# 04-ETHERNET.net
KiCad netlist of a schematic drawn in Altium Designer
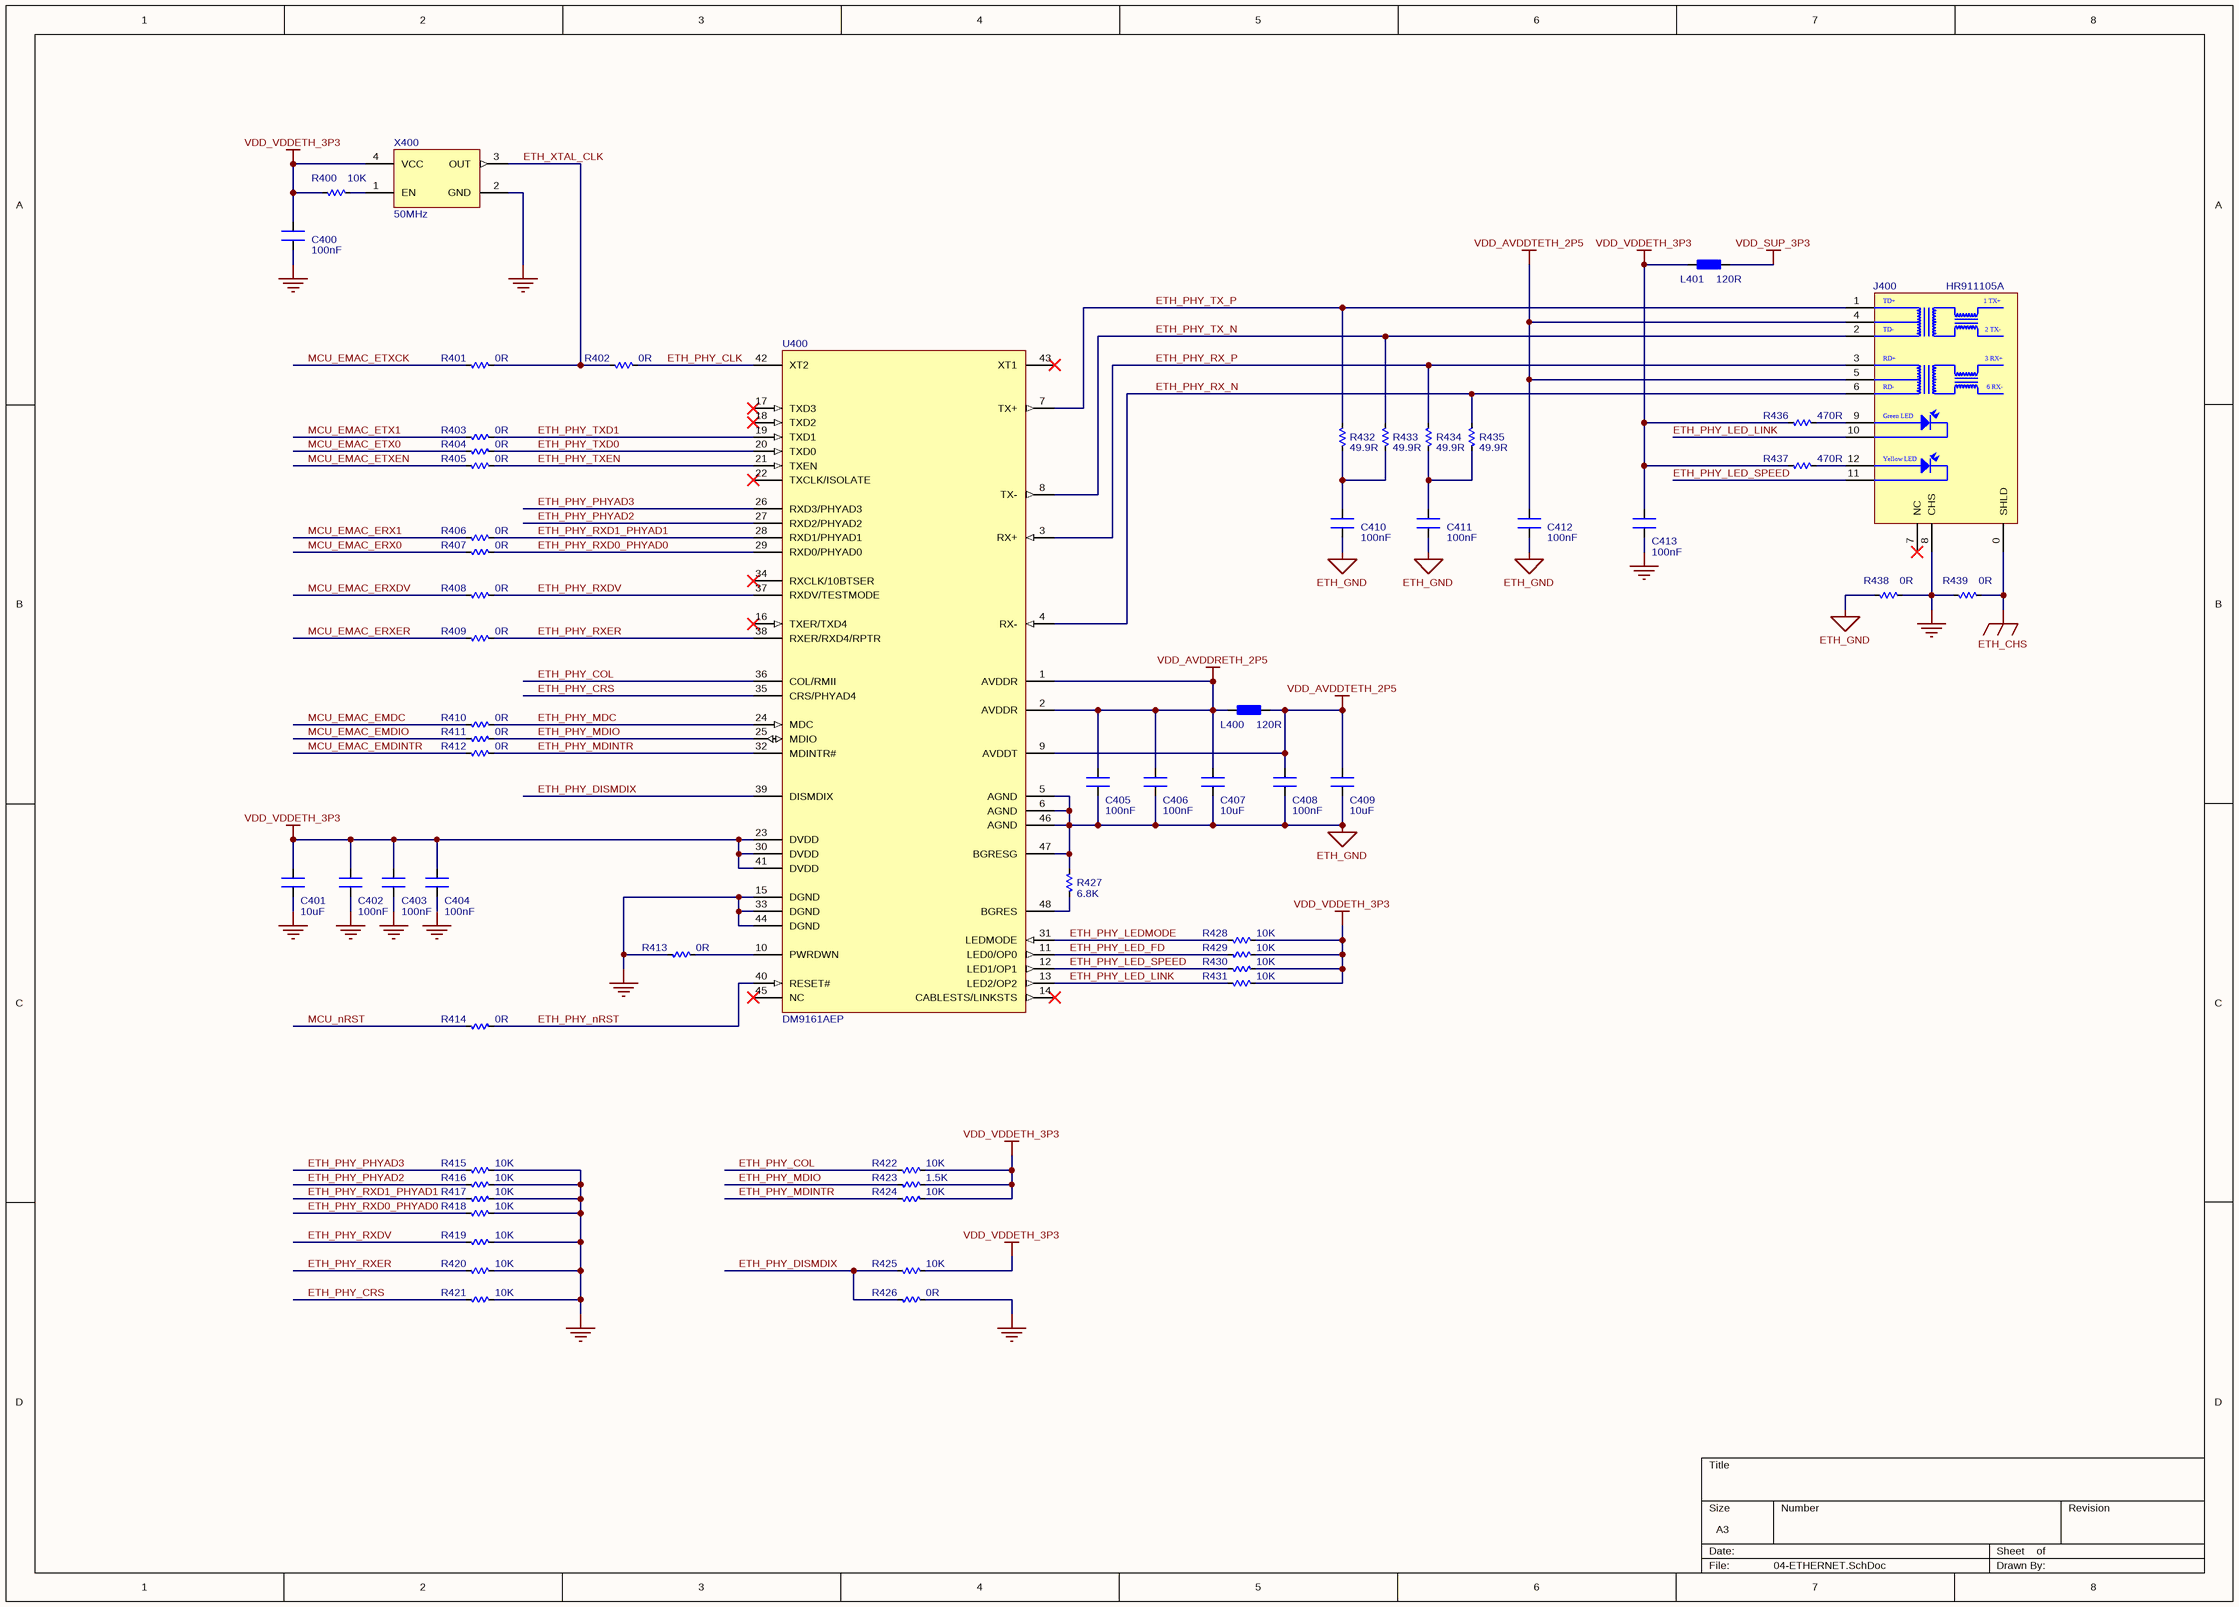
[diagram p0: 04-ETHERNET.SchDoc]

(export (version "E")
  (design (tool "Eeschema 10.0.6"))
  (components
    (comp (ref "C400")
      (value "100nF")
      (footprint "CN-SMD-0603")
      (description "Ceramic Capacitor SMD 0603 100nF ±20% 10V")
      (fields (field (name "Comment") "Capacitor"))
      (libsource (lib "AS50") (part "Cap"))
    )
    (comp (ref "C401")
      (value "10uF")
      (footprint "CN-SMD-0603")
      (description "Ceramic Capacitor SMD 0603 10uF ±20% 10V")
      (fields (field (name "Comment") "Capacitor"))
      (libsource (lib "AS50") (part "Cap"))
    )
    (comp (ref "C402")
      (value "100nF")
      (footprint "CN-SMD-0603")
      (description "Ceramic Capacitor SMD 0603 100nF ±20% 10V")
      (fields (field (name "Comment") "Capacitor"))
      (libsource (lib "AS50") (part "Cap"))
    )
    (comp (ref "C403")
      (value "100nF")
      (footprint "CN-SMD-0603")
      (description "Ceramic Capacitor SMD 0603 100nF ±20% 10V")
      (fields (field (name "Comment") "Capacitor"))
      (libsource (lib "AS50") (part "Cap"))
    )
    (comp (ref "C404")
      (value "100nF")
      (footprint "CN-SMD-0603")
      (description "Ceramic Capacitor SMD 0603 100nF ±20% 10V")
      (fields (field (name "Comment") "Capacitor"))
      (libsource (lib "AS50") (part "Cap"))
    )
    (comp (ref "C405")
      (value "100nF")
      (footprint "CN-SMD-0603")
      (description "Ceramic Capacitor SMD 0603 100nF ±20% 10V")
      (fields (field (name "Comment") "Capacitor"))
      (libsource (lib "AS50") (part "Cap"))
    )
    (comp (ref "C406")
      (value "100nF")
      (footprint "CN-SMD-0603")
      (description "Ceramic Capacitor SMD 0603 100nF ±20% 10V")
      (fields (field (name "Comment") "Capacitor"))
      (libsource (lib "AS50") (part "Cap"))
    )
    (comp (ref "C407")
      (value "10uF")
      (footprint "CN-SMD-0603")
      (description "Ceramic Capacitor SMD 0603 10uF ±20% 10V")
      (fields (field (name "Comment") "Capacitor"))
      (libsource (lib "AS50") (part "Cap"))
    )
    (comp (ref "C408")
      (value "100nF")
      (footprint "CN-SMD-0603")
      (description "Ceramic Capacitor SMD 0603 100nF ±20% 10V")
      (fields (field (name "Comment") "Capacitor"))
      (libsource (lib "AS50") (part "Cap"))
    )
    (comp (ref "C409")
      (value "10uF")
      (footprint "CN-SMD-0603")
      (description "Ceramic Capacitor SMD 0603 10uF ±20% 10V")
      (fields (field (name "Comment") "Capacitor"))
      (libsource (lib "AS50") (part "Cap"))
    )
    (comp (ref "C410")
      (value "100nF")
      (footprint "CN-SMD-0603")
      (description "Ceramic Capacitor SMD 0603 100nF ±20% 10V")
      (fields (field (name "Comment") "Capacitor"))
      (libsource (lib "AS50") (part "Cap"))
    )
    (comp (ref "C411")
      (value "100nF")
      (footprint "CN-SMD-0603")
      (description "Ceramic Capacitor SMD 0603 100nF ±20% 10V")
      (fields (field (name "Comment") "Capacitor"))
      (libsource (lib "AS50") (part "Cap"))
    )
    (comp (ref "C412")
      (value "100nF")
      (footprint "CN-SMD-0603")
      (description "Ceramic Capacitor SMD 0603 100nF ±20% 10V")
      (fields (field (name "Comment") "Capacitor"))
      (libsource (lib "AS50") (part "Cap"))
    )
    (comp (ref "C413")
      (value "100nF")
      (footprint "CN-SMD-0603")
      (description "Ceramic Capacitor SMD 0603 100nF ±20% 10V")
      (fields (field (name "Comment") "Capacitor"))
      (libsource (lib "AS50") (part "Cap"))
    )
    (comp (ref "J400")
      (value "HR911105A")
      (footprint "RJ-45_HR911105A")
      (description "Single port RJ45 Connector with Integrated Magnetics and LED for 10/100-BaseTX NIC Applications")
      (libsource (lib "AS50") (part "HR911105A"))
    )
    (comp (ref "L400")
      (value "120R")
      (footprint "L-SMD-0603")
      (description "Ferrite bead SMD 0603 120 Ohm @100MHz")
      (fields (field (name "Comment") "Ferrite bead"))
      (libsource (lib "AS50") (part "Ferrite bead"))
    )
    (comp (ref "L401")
      (value "120R")
      (footprint "L-SMD-0603")
      (description "Ferrite bead SMD 0603 120 Ohm @100MHz")
      (fields (field (name "Comment") "Ferrite bead"))
      (libsource (lib "AS50") (part "Ferrite bead"))
    )
    (comp (ref "R400")
      (value "10K")
      (footprint "RES-SMD-0603")
      (description "Resistor SMD 0603 10K 1% 0.1W")
      (fields (field (name "Comment") "Resistor"))
      (libsource (lib "AS50") (part "Res"))
    )
    (comp (ref "R401")
      (value "0R")
      (footprint "RES-SMD-0603")
      (description "Resistor SMD 0603 0R 1% 0.1W")
      (fields (field (name "Comment") "Resistor"))
      (libsource (lib "AS50") (part "Res"))
    )
    (comp (ref "R402")
      (value "0R")
      (footprint "RES-SMD-0603")
      (description "Resistor SMD 0603 0R 1% 0.1W")
      (fields (field (name "Comment") "Resistor"))
      (libsource (lib "AS50") (part "Res"))
    )
    (comp (ref "R403")
      (value "0R")
      (footprint "RES-SMD-0603")
      (description "Resistor SMD 0603 0R 1% 0.1W")
      (fields (field (name "Comment") "Resistor"))
      (libsource (lib "AS50") (part "Res"))
    )
    (comp (ref "R404")
      (value "0R")
      (footprint "RES-SMD-0603")
      (description "Resistor SMD 0603 0R 1% 0.1W")
      (fields (field (name "Comment") "Resistor"))
      (libsource (lib "AS50") (part "Res"))
    )
    (comp (ref "R405")
      (value "0R")
      (footprint "RES-SMD-0603")
      (description "Resistor SMD 0603 0R 1% 0.1W")
      (fields (field (name "Comment") "Resistor"))
      (libsource (lib "AS50") (part "Res"))
    )
    (comp (ref "R406")
      (value "0R")
      (footprint "RES-SMD-0603")
      (description "Resistor SMD 0603 0R 1% 0.1W")
      (fields (field (name "Comment") "Resistor"))
      (libsource (lib "AS50") (part "Res"))
    )
    (comp (ref "R407")
      (value "0R")
      (footprint "RES-SMD-0603")
      (description "Resistor SMD 0603 0R 1% 0.1W")
      (fields (field (name "Comment") "Resistor"))
      (libsource (lib "AS50") (part "Res"))
    )
    (comp (ref "R408")
      (value "0R")
      (footprint "RES-SMD-0603")
      (description "Resistor SMD 0603 0R 1% 0.1W")
      (fields (field (name "Comment") "Resistor"))
      (libsource (lib "AS50") (part "Res"))
    )
    (comp (ref "R409")
      (value "0R")
      (footprint "RES-SMD-0603")
      (description "Resistor SMD 0603 0R 1% 0.1W")
      (fields (field (name "Comment") "Resistor"))
      (libsource (lib "AS50") (part "Res"))
    )
    (comp (ref "R410")
      (value "0R")
      (footprint "RES-SMD-0603")
      (description "Resistor SMD 0603 0R 1% 0.1W")
      (fields (field (name "Comment") "Resistor"))
      (libsource (lib "AS50") (part "Res"))
    )
    (comp (ref "R411")
      (value "0R")
      (footprint "RES-SMD-0603")
      (description "Resistor SMD 0603 0R 1% 0.1W")
      (fields (field (name "Comment") "Resistor"))
      (libsource (lib "AS50") (part "Res"))
    )
    (comp (ref "R412")
      (value "0R")
      (footprint "RES-SMD-0603")
      (description "Resistor SMD 0603 0R 1% 0.1W")
      (fields (field (name "Comment") "Resistor"))
      (libsource (lib "AS50") (part "Res"))
    )
    (comp (ref "R413")
      (value "0R")
      (footprint "RES-SMD-0603")
      (description "Resistor SMD 0603 0R 1% 0.1W")
      (fields (field (name "Comment") "Resistor"))
      (libsource (lib "AS50") (part "Res"))
    )
    (comp (ref "R414")
      (value "0R")
      (footprint "RES-SMD-0603")
      (description "Resistor SMD 0603 0R 1% 0.1W")
      (fields (field (name "Comment") "Resistor"))
      (libsource (lib "AS50") (part "Res"))
    )
    (comp (ref "R415")
      (value "10K")
      (footprint "RES-SMD-0603")
      (description "Resistor SMD 0603 10K 1% 0.1W")
      (fields (field (name "Comment") "Resistor"))
      (libsource (lib "AS50") (part "Res"))
    )
    (comp (ref "R416")
      (value "10K")
      (footprint "RES-SMD-0603")
      (description "Resistor SMD 0603 10K 1% 0.1W")
      (fields (field (name "Comment") "Resistor"))
      (libsource (lib "AS50") (part "Res"))
    )
    (comp (ref "R417")
      (value "10K")
      (footprint "RES-SMD-0603")
      (description "Resistor SMD 0603 10K 1% 0.1W")
      (fields (field (name "Comment") "Resistor"))
      (libsource (lib "AS50") (part "Res"))
    )
    (comp (ref "R418")
      (value "10K")
      (footprint "RES-SMD-0603")
      (description "Resistor SMD 0603 10K 1% 0.1W")
      (fields (field (name "Comment") "Resistor"))
      (libsource (lib "AS50") (part "Res"))
    )
    (comp (ref "R419")
      (value "10K")
      (footprint "RES-SMD-0603")
      (description "Resistor SMD 0603 10K 1% 0.1W")
      (fields (field (name "Comment") "Resistor"))
      (libsource (lib "AS50") (part "Res"))
    )
    (comp (ref "R420")
      (value "10K")
      (footprint "RES-SMD-0603")
      (description "Resistor SMD 0603 10K 1% 0.1W")
      (fields (field (name "Comment") "Resistor"))
      (libsource (lib "AS50") (part "Res"))
    )
    (comp (ref "R421")
      (value "10K")
      (footprint "RES-SMD-0603")
      (description "Resistor SMD 0603 10K 1% 0.1W")
      (fields (field (name "Comment") "Resistor"))
      (libsource (lib "AS50") (part "Res"))
    )
    (comp (ref "R422")
      (value "10K")
      (footprint "RES-SMD-0603")
      (description "Resistor SMD 0603 10K 1% 0.1W")
      (fields (field (name "Comment") "Resistor"))
      (libsource (lib "AS50") (part "Res"))
    )
    (comp (ref "R423")
      (value "1.5K")
      (footprint "RES-SMD-0603")
      (description "Resistor SMD 0603 1.5K 1% 0.1W")
      (fields (field (name "Comment") "Resistor"))
      (libsource (lib "AS50") (part "Res"))
    )
    (comp (ref "R424")
      (value "10K")
      (footprint "RES-SMD-0603")
      (description "Resistor SMD 0603 10K 1% 0.1W")
      (fields (field (name "Comment") "Resistor"))
      (libsource (lib "AS50") (part "Res"))
    )
    (comp (ref "R425")
      (value "10K")
      (footprint "RES-SMD-0603")
      (description "Resistor SMD 0603 10K 1% 0.1W")
      (fields (field (name "Comment") "Resistor"))
      (libsource (lib "AS50") (part "Res"))
    )
    (comp (ref "R426")
      (value "0R")
      (footprint "RES-SMD-0603")
      (description "Resistor SMD 0603 0R 1% 0.1W")
      (fields (field (name "Comment") "Resistor"))
      (libsource (lib "AS50") (part "Res"))
    )
    (comp (ref "R427")
      (value "6.8K")
      (footprint "RES-SMD-0603")
      (description "Resistor SMD 0603 6.8K 1% 0.1W")
      (fields (field (name "Comment") "Resistor"))
      (libsource (lib "AS50") (part "Res"))
    )
    (comp (ref "R428")
      (value "10K")
      (footprint "RES-SMD-0603")
      (description "Resistor SMD 0603 10K 1% 0.1W")
      (fields (field (name "Comment") "Resistor"))
      (libsource (lib "AS50") (part "Res"))
    )
    (comp (ref "R429")
      (value "10K")
      (footprint "RES-SMD-0603")
      (description "Resistor SMD 0603 10K 1% 0.1W")
      (fields (field (name "Comment") "Resistor"))
      (libsource (lib "AS50") (part "Res"))
    )
    (comp (ref "R430")
      (value "10K")
      (footprint "RES-SMD-0603")
      (description "Resistor SMD 0603 10K 1% 0.1W")
      (fields (field (name "Comment") "Resistor"))
      (libsource (lib "AS50") (part "Res"))
    )
    (comp (ref "R431")
      (value "10K")
      (footprint "RES-SMD-0603")
      (description "Resistor SMD 0603 10K 1% 0.1W")
      (fields (field (name "Comment") "Resistor"))
      (libsource (lib "AS50") (part "Res"))
    )
    (comp (ref "R432")
      (value "49.9R")
      (footprint "RES-SMD-0603")
      (description "Resistor SMD 0603 49.9R 1% 0.1W")
      (fields (field (name "Comment") "Resistor"))
      (libsource (lib "AS50") (part "Res"))
    )
    (comp (ref "R433")
      (value "49.9R")
      (footprint "RES-SMD-0603")
      (description "Resistor SMD 0603 49.9R 1% 0.1W")
      (fields (field (name "Comment") "Resistor"))
      (libsource (lib "AS50") (part "Res"))
    )
    (comp (ref "R434")
      (value "49.9R")
      (footprint "RES-SMD-0603")
      (description "Resistor SMD 0603 49.9R 1% 0.1W")
      (fields (field (name "Comment") "Resistor"))
      (libsource (lib "AS50") (part "Res"))
    )
    (comp (ref "R435")
      (value "49.9R")
      (footprint "RES-SMD-0603")
      (description "Resistor SMD 0603 49.9R 1% 0.1W")
      (fields (field (name "Comment") "Resistor"))
      (libsource (lib "AS50") (part "Res"))
    )
    (comp (ref "R436")
      (value "470R")
      (footprint "RES-SMD-0603")
      (description "Resistor SMD 0603 470R 1% 0.1W")
      (fields (field (name "Comment") "Resistor"))
      (libsource (lib "AS50") (part "Res"))
    )
    (comp (ref "R437")
      (value "470R")
      (footprint "RES-SMD-0603")
      (description "Resistor SMD 0603 470R 1% 0.1W")
      (fields (field (name "Comment") "Resistor"))
      (libsource (lib "AS50") (part "Res"))
    )
    (comp (ref "R438")
      (value "0R")
      (footprint "RES-SMD-0603")
      (description "Resistor SMD 0603 0R 1% 0.1W")
      (fields (field (name "Comment") "Resistor"))
      (libsource (lib "AS50") (part "Res"))
    )
    (comp (ref "R439")
      (value "0R")
      (footprint "RES-SMD-1206")
      (description "Resistor SMD 1206 0R 1% 0.5W")
      (fields (field (name "Comment") "Resistor"))
      (libsource (lib "AS50") (part "Res"))
    )
    (comp (ref "U400")
      (value "DM9161AEP")
      (footprint "LQFP50P900X900X160-48N")
      (description "DAVICOM 10/100Mbps Fast Ethernet Physical Layer Single Chip Transceiver")
      (libsource (lib "AS50") (part "DM9161AEP"))
    )
    (comp (ref "X400")
      (value "50MHz")
      (footprint "XT-SMD-3225-4P")
      (description "Crystal Oscillator SMD3225 4-pin")
      (libsource (lib "AS50") (part "XT4_2"))
    )
  )
  (nets
    (net (code "1") (name "/ETH_PHY_CLK") (class "Default")
      (node (ref "R402") (pin "1") (pinfunction "1_1") (pintype "passive"))
      (node (ref "U400") (pin "42") (pinfunction "XT2_42") (pintype "passive"))
    )
    (net (code "2") (name "/ETH_PHY_COL") (class "Default")
      (node (ref "R422") (pin "2") (pinfunction "2_2") (pintype "passive"))
      (node (ref "U400") (pin "36") (pinfunction "COL/RMII_36") (pintype "passive"))
    )
    (net (code "3") (name "/ETH_PHY_CRS") (class "Default")
      (node (ref "R421") (pin "2") (pinfunction "2_2") (pintype "passive"))
      (node (ref "U400") (pin "35") (pinfunction "CRS/PHYAD4_35") (pintype "passive"))
    )
    (net (code "4") (name "/ETH_PHY_DISMDIX") (class "Default")
      (node (ref "R425") (pin "2") (pinfunction "2_2") (pintype "passive"))
      (node (ref "R426") (pin "2") (pinfunction "2_2") (pintype "passive"))
      (node (ref "U400") (pin "39") (pinfunction "DISMDIX_39") (pintype "passive"))
    )
    (net (code "5") (name "/ETH_PHY_LEDMODE") (class "Default")
      (node (ref "R428") (pin "2") (pinfunction "2_2") (pintype "passive"))
      (node (ref "U400") (pin "31") (pinfunction "LEDMODE_31") (pintype "input"))
    )
    (net (code "6") (name "/ETH_PHY_LED_FD") (class "Default")
      (node (ref "R429") (pin "2") (pinfunction "2_2") (pintype "passive"))
      (node (ref "U400") (pin "11") (pinfunction "LED0/OP0_11") (pintype "output"))
    )
    (net (code "7") (name "/ETH_PHY_LED_LINK") (class "Default")
      (node (ref "J400") (pin "10") (pinfunction "Green-_10") (pintype "passive"))
      (node (ref "R431") (pin "2") (pinfunction "2_2") (pintype "passive"))
      (node (ref "U400") (pin "13") (pinfunction "LED2/OP2_13") (pintype "output"))
    )
    (net (code "8") (name "/ETH_PHY_LED_SPEED") (class "Default")
      (node (ref "J400") (pin "11") (pinfunction "Yellow-_11") (pintype "passive"))
      (node (ref "R430") (pin "2") (pinfunction "2_2") (pintype "passive"))
      (node (ref "U400") (pin "12") (pinfunction "LED1/OP1_12") (pintype "output"))
    )
    (net (code "9") (name "/ETH_PHY_MDC") (class "Default")
      (node (ref "R410") (pin "1") (pinfunction "1_1") (pintype "passive"))
      (node (ref "U400") (pin "24") (pinfunction "MDC_24") (pintype "input"))
    )
    (net (code "10") (name "/ETH_PHY_MDINTR") (class "Default")
      (node (ref "R412") (pin "1") (pinfunction "1_1") (pintype "passive"))
      (node (ref "R424") (pin "2") (pinfunction "2_2") (pintype "passive"))
      (node (ref "U400") (pin "32") (pinfunction "MDINTR#_32") (pintype "passive"))
    )
    (net (code "11") (name "/ETH_PHY_MDIO") (class "Default")
      (node (ref "R411") (pin "1") (pinfunction "1_1") (pintype "passive"))
      (node (ref "R423") (pin "2") (pinfunction "2_2") (pintype "passive"))
      (node (ref "U400") (pin "25") (pinfunction "MDIO_25") (pintype "bidirectional"))
    )
    (net (code "12") (name "/ETH_PHY_PHYAD2") (class "Default")
      (node (ref "R416") (pin "2") (pinfunction "2_2") (pintype "passive"))
      (node (ref "U400") (pin "27") (pinfunction "RXD2/PHYAD2_27") (pintype "passive"))
    )
    (net (code "13") (name "/ETH_PHY_PHYAD3") (class "Default")
      (node (ref "R415") (pin "2") (pinfunction "2_2") (pintype "passive"))
      (node (ref "U400") (pin "26") (pinfunction "RXD3/PHYAD3_26") (pintype "passive"))
    )
    (net (code "14") (name "/ETH_PHY_RXD0_PHYAD0") (class "Default")
      (node (ref "R407") (pin "1") (pinfunction "1_1") (pintype "passive"))
      (node (ref "R418") (pin "2") (pinfunction "2_2") (pintype "passive"))
      (node (ref "U400") (pin "29") (pinfunction "RXD0/PHYAD0_29") (pintype "passive"))
    )
    (net (code "15") (name "/ETH_PHY_RXD1_PHYAD1") (class "Default")
      (node (ref "R406") (pin "1") (pinfunction "1_1") (pintype "passive"))
      (node (ref "R417") (pin "2") (pinfunction "2_2") (pintype "passive"))
      (node (ref "U400") (pin "28") (pinfunction "RXD1/PHYAD1_28") (pintype "passive"))
    )
    (net (code "16") (name "/ETH_PHY_RXDV") (class "Default")
      (node (ref "R408") (pin "1") (pinfunction "1_1") (pintype "passive"))
      (node (ref "R419") (pin "2") (pinfunction "2_2") (pintype "passive"))
      (node (ref "U400") (pin "37") (pinfunction "RXDV/TESTMODE_37") (pintype "passive"))
    )
    (net (code "17") (name "/ETH_PHY_RXER") (class "Default")
      (node (ref "R409") (pin "1") (pinfunction "1_1") (pintype "passive"))
      (node (ref "R420") (pin "2") (pinfunction "2_2") (pintype "passive"))
      (node (ref "U400") (pin "38") (pinfunction "RXER/RXD4/RPTR_38") (pintype "passive"))
    )
    (net (code "18") (name "/ETH_PHY_RX_N") (class "Default")
      (node (ref "J400") (pin "6") (pinfunction "RD-_6") (pintype "passive"))
      (node (ref "R435") (pin "1") (pinfunction "1_1") (pintype "passive"))
      (node (ref "U400") (pin "4") (pinfunction "RX-_4") (pintype "input"))
    )
    (net (code "19") (name "/ETH_PHY_RX_P") (class "Default")
      (node (ref "J400") (pin "3") (pinfunction "RD+_3") (pintype "passive"))
      (node (ref "R434") (pin "1") (pinfunction "1_1") (pintype "passive"))
      (node (ref "U400") (pin "3") (pinfunction "RX+_3") (pintype "input"))
    )
    (net (code "20") (name "/ETH_PHY_TXD0") (class "Default")
      (node (ref "R404") (pin "1") (pinfunction "1_1") (pintype "passive"))
      (node (ref "U400") (pin "20") (pinfunction "TXD0_20") (pintype "input"))
    )
    (net (code "21") (name "/ETH_PHY_TXD1") (class "Default")
      (node (ref "R403") (pin "1") (pinfunction "1_1") (pintype "passive"))
      (node (ref "U400") (pin "19") (pinfunction "TXD1_19") (pintype "input"))
    )
    (net (code "22") (name "/ETH_PHY_TXEN") (class "Default")
      (node (ref "R405") (pin "1") (pinfunction "1_1") (pintype "passive"))
      (node (ref "U400") (pin "21") (pinfunction "TXEN_21") (pintype "input"))
    )
    (net (code "23") (name "/ETH_PHY_TX_N") (class "Default")
      (node (ref "J400") (pin "2") (pinfunction "TD-_2") (pintype "passive"))
      (node (ref "R433") (pin "1") (pinfunction "1_1") (pintype "passive"))
      (node (ref "U400") (pin "8") (pinfunction "TX-_8") (pintype "output"))
    )
    (net (code "24") (name "/ETH_PHY_TX_P") (class "Default")
      (node (ref "J400") (pin "1") (pinfunction "TD+_1") (pintype "passive"))
      (node (ref "R432") (pin "1") (pinfunction "1_1") (pintype "passive"))
      (node (ref "U400") (pin "7") (pinfunction "TX+_7") (pintype "output"))
    )
    (net (code "25") (name "/ETH_PHY_nRST") (class "Default")
      (node (ref "R414") (pin "1") (pinfunction "1_1") (pintype "passive"))
      (node (ref "U400") (pin "40") (pinfunction "RESET#_40") (pintype "input"))
    )
    (net (code "26") (name "/ETH_XTAL_CLK") (class "Default")
      (node (ref "R401") (pin "1") (pinfunction "1_1") (pintype "passive"))
      (node (ref "R402") (pin "2") (pinfunction "2_2") (pintype "passive"))
      (node (ref "X400") (pin "3") (pinfunction "OUT_3") (pintype "output"))
    )
    (net (code "27") (name "/MCU_EMAC_EMDC") (class "Default")
      (node (ref "R410") (pin "2") (pinfunction "2_2") (pintype "passive"))
    )
    (net (code "28") (name "/MCU_EMAC_EMDINTR") (class "Default")
      (node (ref "R412") (pin "2") (pinfunction "2_2") (pintype "passive"))
    )
    (net (code "29") (name "/MCU_EMAC_EMDIO") (class "Default")
      (node (ref "R411") (pin "2") (pinfunction "2_2") (pintype "passive"))
    )
    (net (code "30") (name "/MCU_EMAC_ERX0") (class "Default")
      (node (ref "R407") (pin "2") (pinfunction "2_2") (pintype "passive"))
    )
    (net (code "31") (name "/MCU_EMAC_ERX1") (class "Default")
      (node (ref "R406") (pin "2") (pinfunction "2_2") (pintype "passive"))
    )
    (net (code "32") (name "/MCU_EMAC_ERXDV") (class "Default")
      (node (ref "R408") (pin "2") (pinfunction "2_2") (pintype "passive"))
    )
    (net (code "33") (name "/MCU_EMAC_ERXER") (class "Default")
      (node (ref "R409") (pin "2") (pinfunction "2_2") (pintype "passive"))
    )
    (net (code "34") (name "/MCU_EMAC_ETX0") (class "Default")
      (node (ref "R404") (pin "2") (pinfunction "2_2") (pintype "passive"))
    )
    (net (code "35") (name "/MCU_EMAC_ETX1") (class "Default")
      (node (ref "R403") (pin "2") (pinfunction "2_2") (pintype "passive"))
    )
    (net (code "36") (name "/MCU_EMAC_ETXCK") (class "Default")
      (node (ref "R401") (pin "2") (pinfunction "2_2") (pintype "passive"))
    )
    (net (code "37") (name "/MCU_EMAC_ETXEN") (class "Default")
      (node (ref "R405") (pin "2") (pinfunction "2_2") (pintype "passive"))
    )
    (net (code "38") (name "/MCU_nRST") (class "Default")
      (node (ref "R414") (pin "2") (pinfunction "2_2") (pintype "passive"))
    )
    (net (code "39") (name "ETH_CHS") (class "Default")
      (node (ref "J400") (pin "0") (pinfunction "SHLD_0") (pintype "passive"))
      (node (ref "R439") (pin "1") (pinfunction "1_1") (pintype "passive"))
    )
    (net (code "40") (name "ETH_GND") (class "Default")
      (node (ref "C405") (pin "1") (pinfunction "1_1") (pintype "passive"))
      (node (ref "C406") (pin "1") (pinfunction "1_1") (pintype "passive"))
      (node (ref "C407") (pin "1") (pinfunction "1_1") (pintype "passive"))
      (node (ref "C408") (pin "1") (pinfunction "1_1") (pintype "passive"))
      (node (ref "C409") (pin "1") (pinfunction "1_1") (pintype "passive"))
      (node (ref "C410") (pin "1") (pinfunction "1_1") (pintype "passive"))
      (node (ref "C411") (pin "1") (pinfunction "1_1") (pintype "passive"))
      (node (ref "C412") (pin "1") (pinfunction "1_1") (pintype "passive"))
      (node (ref "R427") (pin "1") (pinfunction "1_1") (pintype "passive"))
      (node (ref "R438") (pin "2") (pinfunction "2_2") (pintype "passive"))
      (node (ref "U400") (pin "46") (pinfunction "AGND_46") (pintype "power_in"))
      (node (ref "U400") (pin "47") (pinfunction "BGRESG_47") (pintype "passive"))
      (node (ref "U400") (pin "5") (pinfunction "AGND_5") (pintype "power_in"))
      (node (ref "U400") (pin "6") (pinfunction "AGND_6") (pintype "power_in"))
    )
    (net (code "41") (name "GND") (class "Default")
      (node (ref "C400") (pin "1") (pinfunction "1_1") (pintype "passive"))
      (node (ref "C401") (pin "1") (pinfunction "1_1") (pintype "passive"))
      (node (ref "C402") (pin "1") (pinfunction "1_1") (pintype "passive"))
      (node (ref "C403") (pin "1") (pinfunction "1_1") (pintype "passive"))
      (node (ref "C404") (pin "1") (pinfunction "1_1") (pintype "passive"))
      (node (ref "C413") (pin "1") (pinfunction "1_1") (pintype "passive"))
      (node (ref "J400") (pin "8") (pinfunction "CHS_8") (pintype "passive"))
      (node (ref "R413") (pin "2") (pinfunction "2_2") (pintype "passive"))
      (node (ref "R415") (pin "1") (pinfunction "1_1") (pintype "passive"))
      (node (ref "R416") (pin "1") (pinfunction "1_1") (pintype "passive"))
      (node (ref "R417") (pin "1") (pinfunction "1_1") (pintype "passive"))
      (node (ref "R418") (pin "1") (pinfunction "1_1") (pintype "passive"))
      (node (ref "R419") (pin "1") (pinfunction "1_1") (pintype "passive"))
      (node (ref "R420") (pin "1") (pinfunction "1_1") (pintype "passive"))
      (node (ref "R421") (pin "1") (pinfunction "1_1") (pintype "passive"))
      (node (ref "R426") (pin "1") (pinfunction "1_1") (pintype "passive"))
      (node (ref "R438") (pin "1") (pinfunction "1_1") (pintype "passive"))
      (node (ref "R439") (pin "2") (pinfunction "2_2") (pintype "passive"))
      (node (ref "U400") (pin "15") (pinfunction "DGND_15") (pintype "power_in"))
      (node (ref "U400") (pin "33") (pinfunction "DGND_33") (pintype "power_in"))
      (node (ref "U400") (pin "44") (pinfunction "DGND_44") (pintype "power_in"))
      (node (ref "X400") (pin "2") (pinfunction "GND_2") (pintype "power_in"))
    )
    (net (code "42") (name "Net-(C410-Pad2)") (class "Default")
      (node (ref "C410") (pin "2") (pinfunction "2_2") (pintype "passive"))
      (node (ref "R432") (pin "2") (pinfunction "2_2") (pintype "passive"))
      (node (ref "R433") (pin "2") (pinfunction "2_2") (pintype "passive"))
    )
    (net (code "43") (name "Net-(C411-Pad2)") (class "Default")
      (node (ref "C411") (pin "2") (pinfunction "2_2") (pintype "passive"))
      (node (ref "R434") (pin "2") (pinfunction "2_2") (pintype "passive"))
      (node (ref "R435") (pin "2") (pinfunction "2_2") (pintype "passive"))
    )
    (net (code "44") (name "Net-(J400-Green+)") (class "Default")
      (node (ref "J400") (pin "9") (pinfunction "Green+_9") (pintype "passive"))
      (node (ref "R436") (pin "1") (pinfunction "1_1") (pintype "passive"))
    )
    (net (code "45") (name "Net-(J400-Yellow+)") (class "Default")
      (node (ref "J400") (pin "12") (pinfunction "Yellow+_12") (pintype "passive"))
      (node (ref "R437") (pin "1") (pinfunction "1_1") (pintype "passive"))
    )
    (net (code "46") (name "Net-(U400-BGRES)") (class "Default")
      (node (ref "R427") (pin "2") (pinfunction "2_2") (pintype "passive"))
      (node (ref "U400") (pin "48") (pinfunction "BGRES_48") (pintype "passive"))
    )
    (net (code "47") (name "Net-(U400-PWRDWN)") (class "Default")
      (node (ref "R413") (pin "1") (pinfunction "1_1") (pintype "passive"))
      (node (ref "U400") (pin "10") (pinfunction "PWRDWN_10") (pintype "power_in"))
    )
    (net (code "48") (name "Net-(X400-EN)") (class "Default")
      (node (ref "R400") (pin "1") (pinfunction "1_1") (pintype "passive"))
      (node (ref "X400") (pin "1") (pinfunction "EN_1") (pintype "passive"))
    )
    (net (code "49") (name "VDD_AVDDRETH_2P5") (class "Default")
      (node (ref "C405") (pin "2") (pinfunction "2_2") (pintype "passive"))
      (node (ref "C406") (pin "2") (pinfunction "2_2") (pintype "passive"))
      (node (ref "C407") (pin "2") (pinfunction "2_2") (pintype "passive"))
      (node (ref "L400") (pin "2") (pinfunction "2_2") (pintype "passive"))
      (node (ref "U400") (pin "1") (pinfunction "AVDDR_1") (pintype "power_in"))
      (node (ref "U400") (pin "2") (pinfunction "AVDDR_2") (pintype "power_in"))
    )
    (net (code "50") (name "VDD_AVDDTETH_2P5") (class "Default")
      (node (ref "C408") (pin "2") (pinfunction "2_2") (pintype "passive"))
      (node (ref "C409") (pin "2") (pinfunction "2_2") (pintype "passive"))
      (node (ref "C412") (pin "2") (pinfunction "2_2") (pintype "passive"))
      (node (ref "J400") (pin "4") (pinfunction "2,5V_4") (pintype "passive"))
      (node (ref "J400") (pin "5") (pinfunction "2,5V_5") (pintype "passive"))
      (node (ref "L400") (pin "1") (pinfunction "1_1") (pintype "passive"))
      (node (ref "U400") (pin "9") (pinfunction "AVDDT_9") (pintype "power_in"))
    )
    (net (code "51") (name "VDD_SUP_3P3") (class "Default")
      (node (ref "L401") (pin "2") (pinfunction "2_2") (pintype "passive"))
    )
    (net (code "52") (name "VDD_VDDETH_3P3") (class "Default")
      (node (ref "C400") (pin "2") (pinfunction "2_2") (pintype "passive"))
      (node (ref "C401") (pin "2") (pinfunction "2_2") (pintype "passive"))
      (node (ref "C402") (pin "2") (pinfunction "2_2") (pintype "passive"))
      (node (ref "C403") (pin "2") (pinfunction "2_2") (pintype "passive"))
      (node (ref "C404") (pin "2") (pinfunction "2_2") (pintype "passive"))
      (node (ref "C413") (pin "2") (pinfunction "2_2") (pintype "passive"))
      (node (ref "L401") (pin "1") (pinfunction "1_1") (pintype "passive"))
      (node (ref "R400") (pin "2") (pinfunction "2_2") (pintype "passive"))
      (node (ref "R422") (pin "1") (pinfunction "1_1") (pintype "passive"))
      (node (ref "R423") (pin "1") (pinfunction "1_1") (pintype "passive"))
      (node (ref "R424") (pin "1") (pinfunction "1_1") (pintype "passive"))
      (node (ref "R425") (pin "1") (pinfunction "1_1") (pintype "passive"))
      (node (ref "R428") (pin "1") (pinfunction "1_1") (pintype "passive"))
      (node (ref "R429") (pin "1") (pinfunction "1_1") (pintype "passive"))
      (node (ref "R430") (pin "1") (pinfunction "1_1") (pintype "passive"))
      (node (ref "R431") (pin "1") (pinfunction "1_1") (pintype "passive"))
      (node (ref "R436") (pin "2") (pinfunction "2_2") (pintype "passive"))
      (node (ref "R437") (pin "2") (pinfunction "2_2") (pintype "passive"))
      (node (ref "U400") (pin "23") (pinfunction "DVDD_23") (pintype "power_in"))
      (node (ref "U400") (pin "30") (pinfunction "DVDD_30") (pintype "power_in"))
      (node (ref "U400") (pin "41") (pinfunction "DVDD_41") (pintype "power_in"))
      (node (ref "X400") (pin "4") (pinfunction "VCC_4") (pintype "power_in"))
    )
    (net (code "53") (name "unconnected-(J400-NC-Pad7)") (class "Default")
      (node (ref "J400") (pin "7") (pinfunction "NC_7") (pintype "passive+no_connect"))
    )
    (net (code "54") (name "unconnected-(U400-CABLESTS{slash}LINKSTS-Pad14)") (class "Default")
      (node (ref "U400") (pin "14") (pinfunction "CABLESTS/LINKSTS_14") (pintype "output+no_connect"))
    )
    (net (code "55") (name "unconnected-(U400-NC-Pad45)") (class "Default")
      (node (ref "U400") (pin "45") (pinfunction "NC_45") (pintype "passive+no_connect"))
    )
    (net (code "56") (name "unconnected-(U400-RXCLK{slash}10BTSER-Pad34)") (class "Default")
      (node (ref "U400") (pin "34") (pinfunction "RXCLK/10BTSER_34") (pintype "passive+no_connect"))
    )
    (net (code "57") (name "unconnected-(U400-TXCLK{slash}ISOLATE-Pad22)") (class "Default")
      (node (ref "U400") (pin "22") (pinfunction "TXCLK/ISOLATE_22") (pintype "power_in+no_connect"))
    )
    (net (code "58") (name "unconnected-(U400-TXD2-Pad18)") (class "Default")
      (node (ref "U400") (pin "18") (pinfunction "TXD2_18") (pintype "input+no_connect"))
    )
    (net (code "59") (name "unconnected-(U400-TXD3-Pad17)") (class "Default")
      (node (ref "U400") (pin "17") (pinfunction "TXD3_17") (pintype "input+no_connect"))
    )
    (net (code "60") (name "unconnected-(U400-TXER{slash}TXD4-Pad16)") (class "Default")
      (node (ref "U400") (pin "16") (pinfunction "TXER/TXD4_16") (pintype "input+no_connect"))
    )
    (net (code "61") (name "unconnected-(U400-XT1-Pad43)") (class "Default")
      (node (ref "U400") (pin "43") (pinfunction "XT1_43") (pintype "passive+no_connect"))
    )
  )
)
